# P10_ESP32.net
KiCad netlist of a schematic drawn in Altium Designer
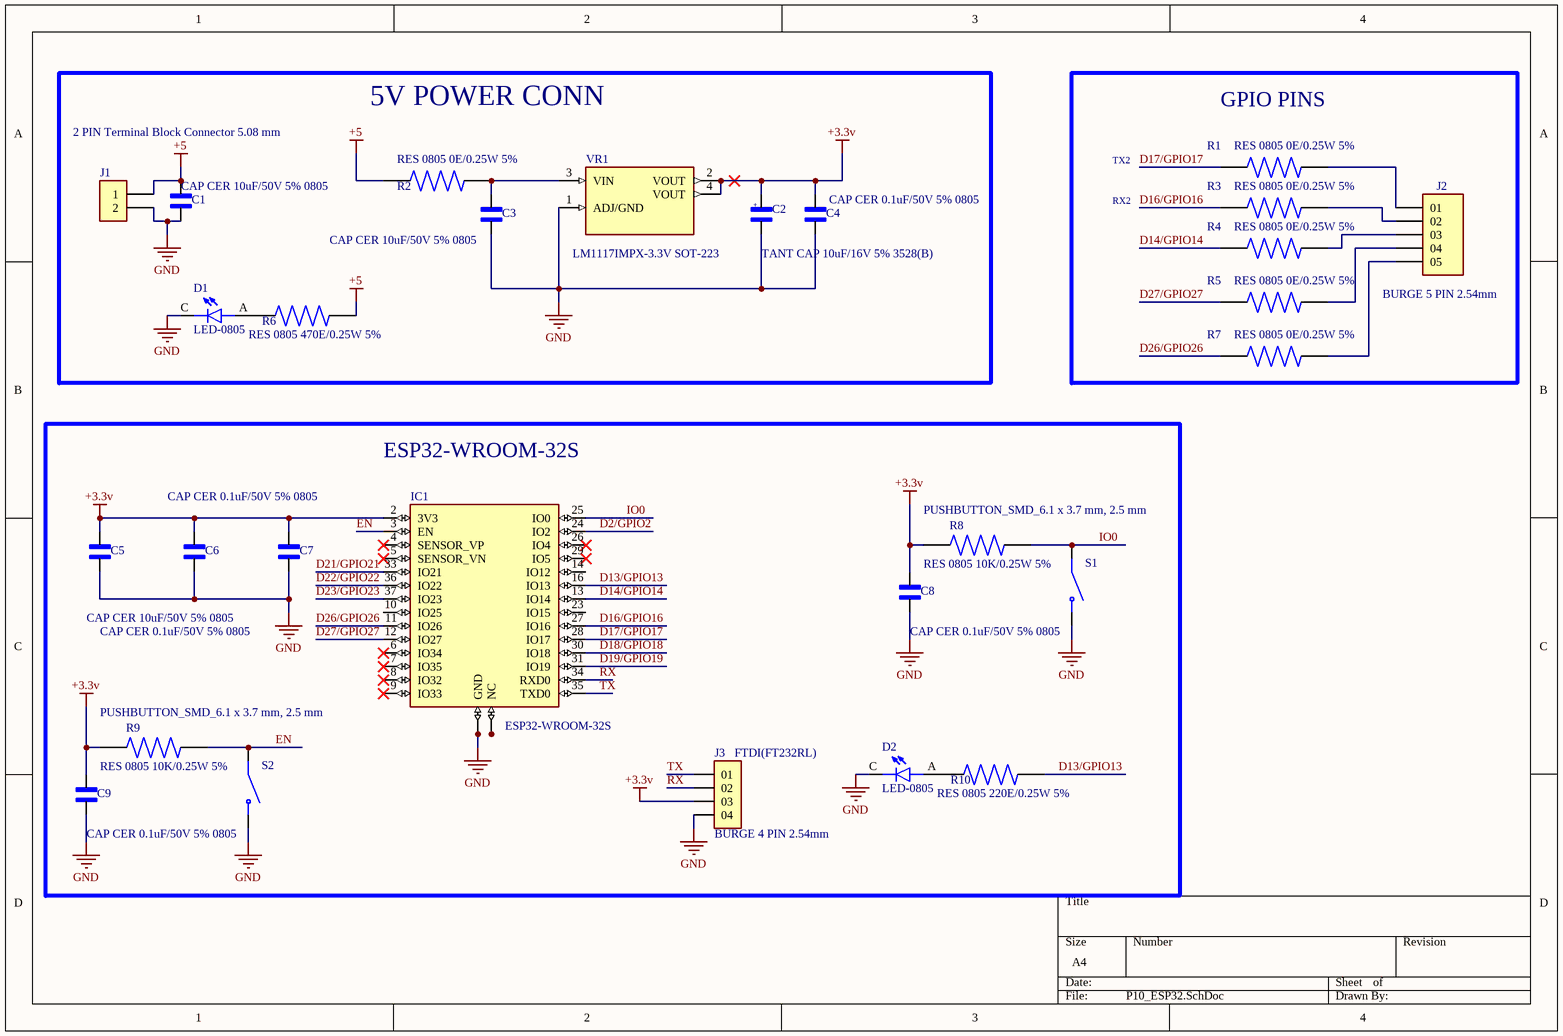
[diagram p0: P10_ESP32.SchDoc]

(export (version "E")
  (design (tool "Eeschema 10.0.6"))
  (components
    (comp (ref "C1")
      (value "CAP CER 10uF/50V 5% 0805")
      (footprint "CAP CER 0.1uF/50V 5%")
      (description "CAP CER 0.1uF/50V  Ceramic Capacitor X7R 0805 (2012 Metric)")
      (fields (field (name "MF") "Samsung") (field (name "MP") "CL21B104KCFNNNE"))
      (libsource (lib "P10_ATMEGA328P") (part "CAP CER 0.1uF/50V 5%"))
    )
    (comp (ref "C2")
      (value "TANT CAP 10uF/16V 5% 3528(B)")
      (footprint "TANT CAP 3528(B)")
      (description "10 ÂµF Molded Tantalum Polymer Capacitor 25 V 1411 (3528 Metric), 1210 150mOhm TCJB106M025R0150")
      (fields (field (name "MF") "AVX") (field (name "MP") "TCJB106M025R0150"))
      (libsource (lib "P10_ESP32") (part "TANT CAP 10uF/16V 5% 3528(B)"))
    )
    (comp (ref "C3")
      (value "CAP CER 10uF/50V 5% 0805")
      (footprint "CAP CER 0.1uF/50V 5%")
      (description "CAP CER 0.1uF/50V  Ceramic Capacitor X7R 0805 (2012 Metric)")
      (fields (field (name "MF") "Samsung") (field (name "MP") "CL21B104KCFNNNE"))
      (libsource (lib "P10_ATMEGA328P") (part "CAP CER 0.1uF/50V 5%"))
    )
    (comp (ref "C4")
      (value "CAP CER 0.1uF/50V 5% 0805")
      (footprint "CAP CER 0.1uF/50V 5%")
      (description "CAP CER 0.1uF/50V  Ceramic Capacitor X7R 0805 (2012 Metric)")
      (fields (field (name "MF") "Samsung") (field (name "MP") "CL21B104KCFNNNE"))
      (libsource (lib "P10_ATMEGA328P") (part "CAP CER 0.1uF/50V 5%"))
    )
    (comp (ref "C5")
      (value "CAP CER 10uF/50V 5% 0805")
      (footprint "CAP CER 0.1uF/50V 5%")
      (description "CAP CER 0.1uF/50V  Ceramic Capacitor X7R 0805 (2012 Metric)")
      (fields (field (name "MF") "Samsung") (field (name "MP") "CL21B104KCFNNNE"))
      (libsource (lib "P10_ATMEGA328P") (part "CAP CER 0.1uF/50V 5%"))
    )
    (comp (ref "C6")
      (value "CAP CER 0.1uF/50V 5% 0805")
      (footprint "CAP CER 0.1uF/50V 5%")
      (description "CAP CER 0.1uF/50V  Ceramic Capacitor X7R 0805 (2012 Metric)")
      (fields (field (name "MF") "Samsung") (field (name "MP") "CL21B104KCFNNNE"))
      (libsource (lib "P10_ATMEGA328P") (part "CAP CER 0.1uF/50V 5%"))
    )
    (comp (ref "C7")
      (value "CAP CER 0.1uF/50V 5% 0805")
      (footprint "CAP CER 0.1uF/50V 5%")
      (description "CAP CER 0.1uF/50V  Ceramic Capacitor X7R 0805 (2012 Metric)")
      (fields (field (name "MF") "Samsung") (field (name "MP") "CL21B104KCFNNNE"))
      (libsource (lib "P10_ATMEGA328P") (part "CAP CER 0.1uF/50V 5%"))
    )
    (comp (ref "C8")
      (value "CAP CER 0.1uF/50V 5% 0805")
      (footprint "CAP CER 0.1uF/50V 5%")
      (description "CAP CER 0.1uF/50V  Ceramic Capacitor X7R 0805 (2012 Metric)")
      (fields (field (name "MF") "Samsung") (field (name "MP") "CL21B104KCFNNNE"))
      (libsource (lib "P10_ATMEGA328P") (part "CAP CER 0.1uF/50V 5%"))
    )
    (comp (ref "C9")
      (value "CAP CER 0.1uF/50V 5% 0805")
      (footprint "CAP CER 0.1uF/50V 5%")
      (description "CAP CER 0.1uF/50V  Ceramic Capacitor X7R 0805 (2012 Metric)")
      (fields (field (name "MF") "Samsung") (field (name "MP") "CL21B104KCFNNNE"))
      (libsource (lib "P10_ATMEGA328P") (part "CAP CER 0.1uF/50V 5%"))
    )
    (comp (ref "D1")
      (value "LED-0805")
      (footprint "LED-0805")
      (description "Red 640nm LED Indication - Discrete 1.85V 0805 (2012 Metric) APT2012SRCPRV")
      (fields (field (name "MF") "Kingbright") (field (name "MP") "APT2012SRCPRV"))
      (libsource (lib "P10_ESP32") (part "LED-0805"))
    )
    (comp (ref "D2")
      (value "LED-0805")
      (footprint "LED-0805")
      (description "Red 640nm LED Indication - Discrete 1.85V 0805 (2012 Metric) APT2012SRCPRV")
      (fields (field (name "MF") "Kingbright") (field (name "MP") "APT2012SRCPRV"))
      (libsource (lib "P10_ESP32") (part "LED-0805"))
    )
    (comp (ref "IC1")
      (value "ESP32-WROOM-32S")
      (footprint "ESP32-WROOM-32S")
      (fields (field (name "MF") "Espressif Systems") (field (name "MP") "ESP32-WROOM-32E-N8"))
      (libsource (lib "P10_ESP32") (part "ESP32-WROOM-32S"))
    )
    (comp (ref "J1")
      (value "2 PIN Terminal Block Connector 5.08 mm")
      (footprint "2 PIN Terminal Block Connector 5.08 mm")
      (description "MOLEX,Screw Type, Horizontal, 5.08 Pitch, 24~12 (AWG), Terminal Block Connector, TB007-508-02BE")
      (fields (field (name "MF") "Same Sky") (field (name "MP") "TB007-508-02BE"))
      (libsource (lib "P10_ATMEGA328P") (part "2 PIN Terminal Block Connector 5.08 mm"))
    )
    (comp (ref "J2")
      (value "BURGE 5 PIN 2.54mm")
      (footprint "BURGE 5 PIN")
      (description "MTSW-105-07-T-S-048 BURGE 5 PIN 2.54mm")
      (fields (field (name "MP") "MTSW-105-07-T-S-048"))
      (libsource (lib "P10_ATMEGA328P") (part "BURGE 5 PIN"))
    )
    (comp (ref "J3")
      (value "BURGE 4 PIN 2.54mm")
      (footprint "BURGE 4 PIN 2.54mm")
      (description "Conn Unshrouded Header HDR 4 POS 2.54mm Solder ST Top Entry Thru-Hole Bulk TSW-104-17-G-S-LL")
      (fields (field (name "MF") "Samtec") (field (name "MP") "TSW-104-23-H-S-LL"))
      (libsource (lib "P10_ESP32") (part "BURGE 4 PIN 2.54mm"))
    )
    (comp (ref "R1")
      (value "RES 0805 0E/0.25W 5%")
      (footprint "RES 0805 10K/0.25W 5%")
      (fields (field (name "MP") "ERJ-6GEYJ103V") (field (name "MF") "Panasonic Electronic"))
      (libsource (lib "P10_ATMEGA328P") (part "RES 0805 10K/0.25W 5%"))
    )
    (comp (ref "R2")
      (value "RES 0805 0E/0.25W 5%")
      (footprint "RES 0805 10K/0.25W 5%")
      (fields (field (name "MP") "ERJ-6GEYJ103V") (field (name "MF") "Panasonic Electronic"))
      (libsource (lib "P10_ATMEGA328P") (part "RES 0805 10K/0.25W 5%"))
    )
    (comp (ref "R3")
      (value "RES 0805 0E/0.25W 5%")
      (footprint "RES 0805 10K/0.25W 5%")
      (fields (field (name "MP") "ERJ-6GEYJ103V") (field (name "MF") "Panasonic Electronic"))
      (libsource (lib "P10_ATMEGA328P") (part "RES 0805 10K/0.25W 5%"))
    )
    (comp (ref "R4")
      (value "RES 0805 0E/0.25W 5%")
      (footprint "RES 0805 10K/0.25W 5%")
      (fields (field (name "MP") "ERJ-6GEYJ103V") (field (name "MF") "Panasonic Electronic"))
      (libsource (lib "P10_ATMEGA328P") (part "RES 0805 10K/0.25W 5%"))
    )
    (comp (ref "R5")
      (value "RES 0805 0E/0.25W 5%")
      (footprint "RES 0805 10K/0.25W 5%")
      (fields (field (name "MP") "ERJ-6GEYJ103V") (field (name "MF") "Panasonic Electronic"))
      (libsource (lib "P10_ATMEGA328P") (part "RES 0805 10K/0.25W 5%"))
    )
    (comp (ref "R6")
      (value "RES 0805 470E/0.25W 5%")
      (footprint "RES 0805 10K/0.25W 5%")
      (fields (field (name "MP") "ERJ-6GEYJ103V") (field (name "MF") "Panasonic Electronic"))
      (libsource (lib "P10_ATMEGA328P") (part "RES 0805 10K/0.25W 5%"))
    )
    (comp (ref "R7")
      (value "RES 0805 0E/0.25W 5%")
      (footprint "RES 0805 10K/0.25W 5%")
      (fields (field (name "MP") "ERJ-6GEYJ103V") (field (name "MF") "Panasonic Electronic"))
      (libsource (lib "P10_ATMEGA328P") (part "RES 0805 10K/0.25W 5%"))
    )
    (comp (ref "R8")
      (value "RES 0805 10K/0.25W 5%")
      (footprint "RES 0805 10K/0.25W 5%")
      (fields (field (name "MP") "ERJ-6GEYJ103V") (field (name "MF") "Panasonic Electronic"))
      (libsource (lib "P10_ATMEGA328P") (part "RES 0805 10K/0.25W 5%"))
    )
    (comp (ref "R9")
      (value "RES 0805 10K/0.25W 5%")
      (footprint "RES 0805 10K/0.25W 5%")
      (fields (field (name "MP") "ERJ-6GEYJ103V") (field (name "MF") "Panasonic Electronic"))
      (libsource (lib "P10_ATMEGA328P") (part "RES 0805 10K/0.25W 5%"))
    )
    (comp (ref "R10")
      (value "RES 0805 220E/0.25W 5%")
      (footprint "RES 0805 10K/0.25W 5%")
      (fields (field (name "MP") "ERJ-6GEYJ103V") (field (name "MF") "Panasonic Electronic"))
      (libsource (lib "P10_ATMEGA328P") (part "RES 0805 10K/0.25W 5%"))
    )
    (comp (ref "S1")
      (value "PUSHBUTTON_SMD_6.1 x 3.7 mm, 2.5 mm")
      (footprint "PUSHBUTTON_SMD_6.1 x 3.7 mm, 2.5 mm")
      (fields (field (name "MF") "Same Sky") (field (name "MP") "TS09-63-25-R-260-SMT-TR"))
      (libsource (lib "P10_ATMEGA328P") (part "PUSHBUTTON_SMD_6.1 x 3.7 mm, 2.5 mm"))
    )
    (comp (ref "S2")
      (value "PUSHBUTTON_SMD_6.1 x 3.7 mm, 2.5 mm")
      (footprint "PUSHBUTTON_SMD_6.1 x 3.7 mm, 2.5 mm")
      (fields (field (name "MF") "Same Sky") (field (name "MP") "TS09-63-25-R-260-SMT-TR"))
      (libsource (lib "P10_ATMEGA328P") (part "PUSHBUTTON_SMD_6.1 x 3.7 mm, 2.5 mm"))
    )
    (comp (ref "VR1")
      (value "LM1117IMPX-3.3V SOT-223")
      (footprint "LM1117IMPX-3.3V SOT-223")
      (description "LM1117IMPX-3.3V 800-mA 15-V linear voltage regulator SOT-223")
      (fields (field (name "MF") "Texas Instruments") (field (name "MP") "LM1117IMPX-5.0/NOPB"))
      (libsource (lib "P10_ESP32") (part "LM1117IMPX-3.3V SOT-223"))
    )
  )
  (nets
    (net (code "1") (name "+3.3v") (class "Default")
      (node (ref "C2") (pin "1") (pinfunction "1_1") (pintype "passive"))
      (node (ref "C4") (pin "2") (pinfunction "2_2") (pintype "passive"))
      (node (ref "C5") (pin "2") (pinfunction "2_2") (pintype "passive"))
      (node (ref "C6") (pin "2") (pinfunction "2_2") (pintype "passive"))
      (node (ref "C7") (pin "2") (pinfunction "2_2") (pintype "passive"))
      (node (ref "C8") (pin "2") (pinfunction "2_2") (pintype "passive"))
      (node (ref "C9") (pin "2") (pinfunction "2_2") (pintype "passive"))
      (node (ref "IC1") (pin "2") (pinfunction "3V3_2") (pintype "bidirectional"))
      (node (ref "J3") (pin "03") (pinfunction "03_03") (pintype "passive"))
      (node (ref "R8") (pin "1") (pinfunction "1_1") (pintype "passive"))
      (node (ref "R9") (pin "1") (pinfunction "1_1") (pintype "passive"))
      (node (ref "VR1") (pin "2") (pinfunction "VOUT_2") (pintype "output"))
      (node (ref "VR1") (pin "4") (pinfunction "VOUT_4") (pintype "output"))
    )
    (net (code "2") (name "+5") (class "Default")
      (node (ref "C1") (pin "2") (pinfunction "2_2") (pintype "passive"))
      (node (ref "J1") (pin "1") (pinfunction "1_1") (pintype "passive"))
      (node (ref "R2") (pin "1") (pinfunction "1_1") (pintype "passive"))
      (node (ref "R6") (pin "2") (pinfunction "2_2") (pintype "passive"))
    )
    (net (code "3") (name "/D2{slash}GPIO2") (class "Default")
      (node (ref "IC1") (pin "24") (pinfunction "IO2_24") (pintype "bidirectional"))
    )
    (net (code "4") (name "/D13{slash}GPIO13") (class "Default")
      (node (ref "IC1") (pin "16") (pinfunction "IO13_16") (pintype "bidirectional"))
      (node (ref "R10") (pin "2") (pinfunction "2_2") (pintype "passive"))
    )
    (net (code "5") (name "/D14{slash}GPIO14") (class "Default")
      (node (ref "IC1") (pin "13") (pinfunction "IO14_13") (pintype "bidirectional"))
      (node (ref "R4") (pin "1") (pinfunction "1_1") (pintype "passive"))
    )
    (net (code "6") (name "/D16{slash}GPIO16") (class "Default")
      (node (ref "IC1") (pin "27") (pinfunction "IO16_27") (pintype "bidirectional"))
      (node (ref "R3") (pin "1") (pinfunction "1_1") (pintype "passive"))
    )
    (net (code "7") (name "/D17{slash}GPIO17") (class "Default")
      (node (ref "IC1") (pin "28") (pinfunction "IO17_28") (pintype "bidirectional"))
      (node (ref "R1") (pin "1") (pinfunction "1_1") (pintype "passive"))
    )
    (net (code "8") (name "/D18{slash}GPIO18") (class "Default")
      (node (ref "IC1") (pin "30") (pinfunction "IO18_30") (pintype "bidirectional"))
    )
    (net (code "9") (name "/D19{slash}GPIO19") (class "Default")
      (node (ref "IC1") (pin "31") (pinfunction "IO19_31") (pintype "bidirectional"))
    )
    (net (code "10") (name "/D21{slash}GPIO21") (class "Default")
      (node (ref "IC1") (pin "33") (pinfunction "IO21_33") (pintype "bidirectional"))
    )
    (net (code "11") (name "/D22{slash}GPIO22") (class "Default")
      (node (ref "IC1") (pin "36") (pinfunction "IO22_36") (pintype "bidirectional"))
    )
    (net (code "12") (name "/D23{slash}GPIO23") (class "Default")
      (node (ref "IC1") (pin "37") (pinfunction "IO23_37") (pintype "bidirectional"))
    )
    (net (code "13") (name "/D26{slash}GPIO26") (class "Default")
      (node (ref "IC1") (pin "11") (pinfunction "IO26_11") (pintype "bidirectional"))
      (node (ref "R7") (pin "1") (pinfunction "1_1") (pintype "passive"))
    )
    (net (code "14") (name "/D27{slash}GPIO27") (class "Default")
      (node (ref "IC1") (pin "12") (pinfunction "IO27_12") (pintype "bidirectional"))
      (node (ref "R5") (pin "1") (pinfunction "1_1") (pintype "passive"))
    )
    (net (code "15") (name "/EN") (class "Default")
      (node (ref "IC1") (pin "3") (pinfunction "EN_3") (pintype "bidirectional"))
      (node (ref "R9") (pin "2") (pinfunction "2_2") (pintype "passive"))
      (node (ref "S2") (pin "1") (pinfunction "1_1") (pintype "passive"))
    )
    (net (code "16") (name "/IO0") (class "Default")
      (node (ref "IC1") (pin "25") (pinfunction "IO0_25") (pintype "bidirectional"))
      (node (ref "R8") (pin "2") (pinfunction "2_2") (pintype "passive"))
      (node (ref "S1") (pin "1") (pinfunction "1_1") (pintype "passive"))
    )
    (net (code "17") (name "/RX") (class "Default")
      (node (ref "IC1") (pin "34") (pinfunction "RXD0_34") (pintype "bidirectional"))
      (node (ref "J3") (pin "02") (pinfunction "02_02") (pintype "passive"))
    )
    (net (code "18") (name "/TX") (class "Default")
      (node (ref "IC1") (pin "35") (pinfunction "TXD0_35") (pintype "bidirectional"))
      (node (ref "J3") (pin "01") (pinfunction "01_01") (pintype "passive"))
    )
    (net (code "19") (name "GND") (class "Default")
      (node (ref "C1") (pin "1") (pinfunction "1_1") (pintype "passive"))
      (node (ref "C2") (pin "2") (pinfunction "2_2") (pintype "passive"))
      (node (ref "C3") (pin "1") (pinfunction "1_1") (pintype "passive"))
      (node (ref "C4") (pin "1") (pinfunction "1_1") (pintype "passive"))
      (node (ref "C5") (pin "1") (pinfunction "1_1") (pintype "passive"))
      (node (ref "C6") (pin "1") (pinfunction "1_1") (pintype "passive"))
      (node (ref "C7") (pin "1") (pinfunction "1_1") (pintype "passive"))
      (node (ref "C8") (pin "1") (pinfunction "1_1") (pintype "passive"))
      (node (ref "C9") (pin "1") (pinfunction "1_1") (pintype "passive"))
      (node (ref "D1") (pin "C") (pinfunction "C_C") (pintype "passive"))
      (node (ref "D2") (pin "C") (pinfunction "C_C") (pintype "passive"))
      (node (ref "IC1") (pin "1") (pinfunction "GND_1") (pintype "bidirectional"))
      (node (ref "IC1") (pin "15") (pinfunction "GND_15") (pintype "bidirectional"))
      (node (ref "IC1") (pin "38") (pinfunction "GND_38") (pintype "bidirectional"))
      (node (ref "IC1") (pin "39") (pinfunction "GND_39") (pintype "bidirectional"))
      (node (ref "IC1") (pin "40") (pinfunction "GND_40") (pintype "bidirectional"))
      (node (ref "IC1") (pin "41") (pinfunction "GND_41") (pintype "bidirectional"))
      (node (ref "IC1") (pin "42") (pinfunction "GND_42") (pintype "bidirectional"))
      (node (ref "IC1") (pin "43") (pinfunction "GND_43") (pintype "bidirectional"))
      (node (ref "IC1") (pin "44") (pinfunction "GND_44") (pintype "bidirectional"))
      (node (ref "IC1") (pin "45") (pinfunction "GND_45") (pintype "bidirectional"))
      (node (ref "IC1") (pin "46") (pinfunction "GND_46") (pintype "bidirectional"))
      (node (ref "IC1") (pin "47") (pinfunction "GND_47") (pintype "bidirectional"))
      (node (ref "J1") (pin "2") (pinfunction "2_2") (pintype "passive"))
      (node (ref "J3") (pin "04") (pinfunction "04_04") (pintype "passive"))
      (node (ref "S1") (pin "2") (pinfunction "2_2") (pintype "passive"))
      (node (ref "S2") (pin "2") (pinfunction "2_2") (pintype "passive"))
      (node (ref "VR1") (pin "1") (pinfunction "ADJ/GND_1") (pintype "input"))
    )
    (net (code "20") (name "Net-(D1-PadA)") (class "Default")
      (node (ref "D1") (pin "A") (pinfunction "A_A") (pintype "passive"))
      (node (ref "R6") (pin "1") (pinfunction "1_1") (pintype "passive"))
    )
    (net (code "21") (name "Net-(D2-PadA)") (class "Default")
      (node (ref "D2") (pin "A") (pinfunction "A_A") (pintype "passive"))
      (node (ref "R10") (pin "1") (pinfunction "1_1") (pintype "passive"))
    )
    (net (code "22") (name "Net-(IC1-NC-Pad17)") (class "Default")
      (node (ref "IC1") (pin "17") (pinfunction "NC_17") (pintype "bidirectional"))
      (node (ref "IC1") (pin "18") (pinfunction "NC_18") (pintype "bidirectional"))
      (node (ref "IC1") (pin "19") (pinfunction "NC_19") (pintype "bidirectional"))
      (node (ref "IC1") (pin "20") (pinfunction "NC_20") (pintype "bidirectional"))
      (node (ref "IC1") (pin "21") (pinfunction "NC_21") (pintype "bidirectional"))
      (node (ref "IC1") (pin "22") (pinfunction "NC_22") (pintype "bidirectional"))
      (node (ref "IC1") (pin "32") (pinfunction "NC_32") (pintype "bidirectional"))
    )
    (net (code "23") (name "Net-(J2-Pad01)") (class "Default")
      (node (ref "J2") (pin "01") (pinfunction "01_01") (pintype "passive"))
      (node (ref "R1") (pin "2") (pinfunction "2_2") (pintype "passive"))
    )
    (net (code "24") (name "Net-(J2-Pad02)") (class "Default")
      (node (ref "J2") (pin "02") (pinfunction "02_02") (pintype "passive"))
      (node (ref "R3") (pin "2") (pinfunction "2_2") (pintype "passive"))
    )
    (net (code "25") (name "Net-(J2-Pad03)") (class "Default")
      (node (ref "J2") (pin "03") (pinfunction "03_03") (pintype "passive"))
      (node (ref "R4") (pin "2") (pinfunction "2_2") (pintype "passive"))
    )
    (net (code "26") (name "Net-(J2-Pad04)") (class "Default")
      (node (ref "J2") (pin "04") (pinfunction "04_04") (pintype "passive"))
      (node (ref "R5") (pin "2") (pinfunction "2_2") (pintype "passive"))
    )
    (net (code "27") (name "Net-(J2-Pad05)") (class "Default")
      (node (ref "J2") (pin "05") (pinfunction "05_05") (pintype "passive"))
      (node (ref "R7") (pin "2") (pinfunction "2_2") (pintype "passive"))
    )
    (net (code "28") (name "Net-(VR1-VIN)") (class "Default")
      (node (ref "C3") (pin "2") (pinfunction "2_2") (pintype "passive"))
      (node (ref "R2") (pin "2") (pinfunction "2_2") (pintype "passive"))
      (node (ref "VR1") (pin "3") (pinfunction "VIN_3") (pintype "input"))
    )
    (net (code "29") (name "unconnected-(IC1-IO4-Pad26)") (class "Default")
      (node (ref "IC1") (pin "26") (pinfunction "IO4_26") (pintype "bidirectional+no_connect"))
    )
    (net (code "30") (name "unconnected-(IC1-IO5-Pad29)") (class "Default")
      (node (ref "IC1") (pin "29") (pinfunction "IO5_29") (pintype "bidirectional+no_connect"))
    )
    (net (code "31") (name "unconnected-(IC1-IO12-Pad14)") (class "Default")
      (node (ref "IC1") (pin "14") (pinfunction "IO12_14") (pintype "bidirectional"))
    )
    (net (code "32") (name "unconnected-(IC1-IO15-Pad23)") (class "Default")
      (node (ref "IC1") (pin "23") (pinfunction "IO15_23") (pintype "bidirectional"))
    )
    (net (code "33") (name "unconnected-(IC1-IO25-Pad10)") (class "Default")
      (node (ref "IC1") (pin "10") (pinfunction "IO25_10") (pintype "bidirectional"))
    )
    (net (code "34") (name "unconnected-(IC1-IO32-Pad8)") (class "Default")
      (node (ref "IC1") (pin "8") (pinfunction "IO32_8") (pintype "bidirectional+no_connect"))
    )
    (net (code "35") (name "unconnected-(IC1-IO33-Pad9)") (class "Default")
      (node (ref "IC1") (pin "9") (pinfunction "IO33_9") (pintype "bidirectional+no_connect"))
    )
    (net (code "36") (name "unconnected-(IC1-IO34-Pad6)") (class "Default")
      (node (ref "IC1") (pin "6") (pinfunction "IO34_6") (pintype "bidirectional+no_connect"))
    )
    (net (code "37") (name "unconnected-(IC1-IO35-Pad7)") (class "Default")
      (node (ref "IC1") (pin "7") (pinfunction "IO35_7") (pintype "bidirectional+no_connect"))
    )
    (net (code "38") (name "unconnected-(IC1-SENSOR_VN-Pad5)") (class "Default")
      (node (ref "IC1") (pin "5") (pinfunction "SENSOR_VN_5") (pintype "bidirectional+no_connect"))
    )
    (net (code "39") (name "unconnected-(IC1-SENSOR_VP-Pad4)") (class "Default")
      (node (ref "IC1") (pin "4") (pinfunction "SENSOR_VP_4") (pintype "bidirectional+no_connect"))
    )
  )
)
